# Main.net
KiCad netlist of a schematic drawn in Altium Designer
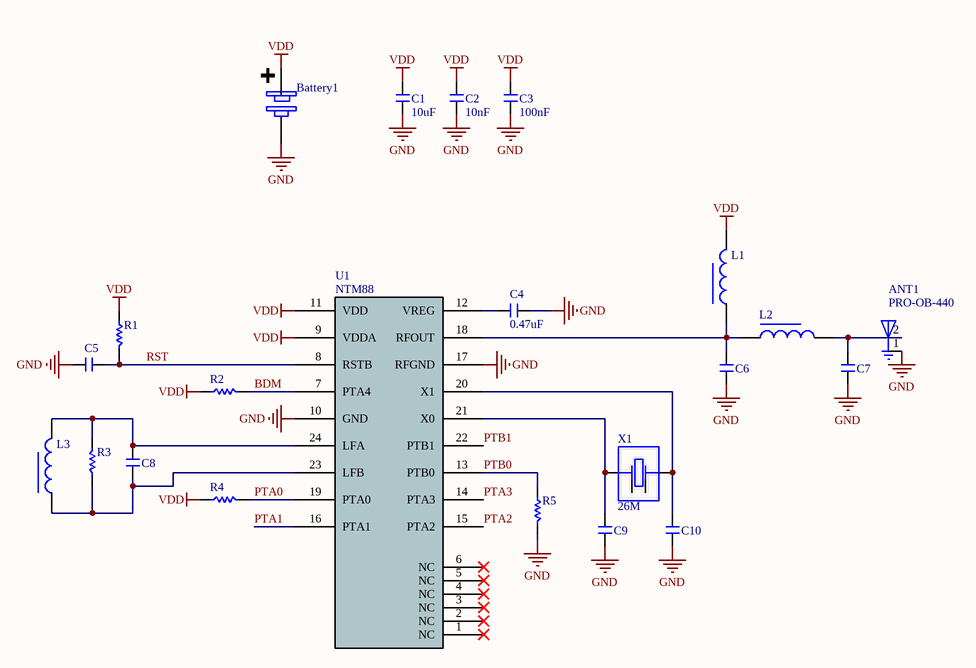
[diagram p0: Main.SchDoc]

(export (version "E")
  (design (tool "Eeschema 10.0.6"))
  (components
    (comp (ref "ANT1")
      (value "PRO-OB-440")
      (footprint "PRO-OB-440")
      (libsource (lib "Antenna") (part "PRO-OB-440"))
    )
    (comp (ref "Battery1")
      (value "Battery Button Cell")
      (footprint "CR1220_B")
      (description "Mini Battery")
      (libsource (lib "Battery Holder") (part "Battery Button Cell"))
    )
    (comp (ref "C1")
      (value "10uF")
      (footprint "C 0603")
      (description "Non-polar patch capacitor")
      (fields (field (name "版权归属") "源创客"))
      (libsource (lib "Passive (Resistor-Capacitor-Inductor-Veristor-Ferrite)") (part "C"))
    )
    (comp (ref "C2")
      (value "10nF")
      (footprint "C 0603")
      (description "Non-polar patch capacitor")
      (fields (field (name "版权归属") "源创客"))
      (libsource (lib "Passive (Resistor-Capacitor-Inductor-Veristor-Ferrite)") (part "C"))
    )
    (comp (ref "C3")
      (value "100nF")
      (footprint "C 0603")
      (description "Non-polar patch capacitor")
      (fields (field (name "版权归属") "源创客"))
      (libsource (lib "Passive (Resistor-Capacitor-Inductor-Veristor-Ferrite)") (part "C"))
    )
    (comp (ref "C4")
      (value "0.47uF")
      (footprint "C 0603")
      (description "Non-polar patch capacitor")
      (fields (field (name "版权归属") "源创客"))
      (libsource (lib "Passive (Resistor-Capacitor-Inductor-Veristor-Ferrite)") (part "C"))
    )
    (comp (ref "C5")
      (value "?")
      (footprint "C 0603")
      (description "Non-polar patch capacitor")
      (fields (field (name "版权归属") "源创客"))
      (libsource (lib "Passive (Resistor-Capacitor-Inductor-Veristor-Ferrite)") (part "C"))
    )
    (comp (ref "C6")
      (value "?")
      (footprint "C 0603")
      (description "Non-polar patch capacitor")
      (fields (field (name "版权归属") "源创客"))
      (libsource (lib "Passive (Resistor-Capacitor-Inductor-Veristor-Ferrite)") (part "C"))
    )
    (comp (ref "C7")
      (value "?")
      (footprint "C 0603")
      (description "Non-polar patch capacitor")
      (fields (field (name "版权归属") "源创客"))
      (libsource (lib "Passive (Resistor-Capacitor-Inductor-Veristor-Ferrite)") (part "C"))
    )
    (comp (ref "C8")
      (value "?")
      (footprint "C 0603")
      (description "Non-polar patch capacitor")
      (fields (field (name "版权归属") "源创客"))
      (libsource (lib "Passive (Resistor-Capacitor-Inductor-Veristor-Ferrite)") (part "C"))
    )
    (comp (ref "C9")
      (value "CRYSTAL REC")
      (footprint "C 0603")
      (description "Non-polar patch capacitor")
      (fields (field (name "版权归属") "源创客"))
      (libsource (lib "Passive (Resistor-Capacitor-Inductor-Veristor-Ferrite)") (part "C"))
    )
    (comp (ref "C10")
      (value "CRYSTAL REC")
      (footprint "C 0603")
      (description "Non-polar patch capacitor")
      (fields (field (name "版权归属") "源创客"))
      (libsource (lib "Passive (Resistor-Capacitor-Inductor-Veristor-Ferrite)") (part "C"))
    )
    (comp (ref "L1")
      (value "?uH")
      (footprint "L 0603")
      (description "Low power chip inductor")
      (fields (field (name "版权归属") "源创客"))
      (libsource (lib "Passive (Resistor-Capacitor-Inductor-Veristor-Ferrite)") (part "L"))
    )
    (comp (ref "L2")
      (value "?uH")
      (footprint "L 0603")
      (description "Low power chip inductor")
      (fields (field (name "版权归属") "源创客"))
      (libsource (lib "Passive (Resistor-Capacitor-Inductor-Veristor-Ferrite)") (part "L"))
    )
    (comp (ref "L3")
      (value "?uH")
      (footprint "L 0603")
      (description "Low power chip inductor")
      (fields (field (name "版权归属") "源创客"))
      (libsource (lib "Passive (Resistor-Capacitor-Inductor-Veristor-Ferrite)") (part "L"))
    )
    (comp (ref "R1")
      (value "?")
      (footprint "R 0603")
      (description "Chip resistor")
      (fields (field (name "版权归属") "源创客"))
      (libsource (lib "Passive (Resistor-Capacitor-Inductor-Veristor-Ferrite)") (part "R"))
    )
    (comp (ref "R2")
      (value "?")
      (footprint "R 0603")
      (description "Chip resistor")
      (fields (field (name "版权归属") "源创客"))
      (libsource (lib "Passive (Resistor-Capacitor-Inductor-Veristor-Ferrite)") (part "R"))
    )
    (comp (ref "R3")
      (value "?")
      (footprint "R 0603")
      (description "Chip resistor")
      (fields (field (name "版权归属") "源创客"))
      (libsource (lib "Passive (Resistor-Capacitor-Inductor-Veristor-Ferrite)") (part "R"))
    )
    (comp (ref "R4")
      (value "?")
      (footprint "R 0603")
      (description "Chip resistor")
      (fields (field (name "版权归属") "源创客"))
      (libsource (lib "Passive (Resistor-Capacitor-Inductor-Veristor-Ferrite)") (part "R"))
    )
    (comp (ref "R5")
      (value "1K")
      (footprint "R 0603")
      (description "Chip resistor")
      (fields (field (name "版权归属") "源创客"))
      (libsource (lib "Passive (Resistor-Capacitor-Inductor-Veristor-Ferrite)") (part "R"))
    )
    (comp (ref "U1")
      (value "NTM88")
      (footprint "QFN24")
      (description "TPMS Sensor")
      (libsource (lib "Integrated Circuit") (part "NTM88"))
    )
    (comp (ref "X1")
      (value "26M")
      (footprint "XTAL-2520-4")
      (description "4-Pin crystal")
      (fields (field (name "版权归属") "源创客"))
      (libsource (lib "Crystal Oscillator") (part "XTAL-4"))
    )
  )
  (nets
    (net (code "1") (name "/BDM") (class "Default")
      (node (ref "R2") (pin "2") (pinfunction "2_2") (pintype "passive"))
      (node (ref "U1") (pin "7") (pinfunction "PTA4_7") (pintype "passive"))
    )
    (net (code "2") (name "/PTA0") (class "Default")
      (node (ref "R4") (pin "2") (pinfunction "2_2") (pintype "passive"))
      (node (ref "U1") (pin "19") (pinfunction "PTA0_19") (pintype "passive"))
    )
    (net (code "3") (name "/PTA1") (class "Default")
      (node (ref "U1") (pin "16") (pinfunction "PTA1_16") (pintype "passive"))
    )
    (net (code "4") (name "/PTA2") (class "Default")
      (node (ref "U1") (pin "15") (pinfunction "PTA2_15") (pintype "passive"))
    )
    (net (code "5") (name "/PTA3") (class "Default")
      (node (ref "U1") (pin "14") (pinfunction "PTA3_14") (pintype "passive"))
    )
    (net (code "6") (name "/PTB0") (class "Default")
      (node (ref "R5") (pin "1") (pinfunction "1_1") (pintype "passive"))
      (node (ref "U1") (pin "13") (pinfunction "PTB0_13") (pintype "passive"))
    )
    (net (code "7") (name "/PTB1") (class "Default")
      (node (ref "U1") (pin "22") (pinfunction "PTB1_22") (pintype "passive"))
    )
    (net (code "8") (name "/RST") (class "Default")
      (node (ref "C5") (pin "2") (pinfunction "2_2") (pintype "passive"))
      (node (ref "R1") (pin "2") (pinfunction "2_2") (pintype "passive"))
      (node (ref "U1") (pin "8") (pinfunction "RSTB_8") (pintype "passive"))
    )
    (net (code "9") (name "GND") (class "Default")
      (node (ref "ANT1") (pin "1") (pinfunction "GND_1") (pintype "power_in"))
      (node (ref "Battery1") (pin "2") (pinfunction "-_2") (pintype "passive"))
      (node (ref "C1") (pin "1") (pinfunction "1_1") (pintype "passive"))
      (node (ref "C10") (pin "1") (pinfunction "1_1") (pintype "passive"))
      (node (ref "C2") (pin "1") (pinfunction "1_1") (pintype "passive"))
      (node (ref "C3") (pin "1") (pinfunction "1_1") (pintype "passive"))
      (node (ref "C4") (pin "1") (pinfunction "1_1") (pintype "passive"))
      (node (ref "C5") (pin "1") (pinfunction "1_1") (pintype "passive"))
      (node (ref "C6") (pin "1") (pinfunction "1_1") (pintype "passive"))
      (node (ref "C7") (pin "1") (pinfunction "1_1") (pintype "passive"))
      (node (ref "C9") (pin "1") (pinfunction "1_1") (pintype "passive"))
      (node (ref "R5") (pin "2") (pinfunction "2_2") (pintype "passive"))
      (node (ref "U1") (pin "10") (pinfunction "GND_10") (pintype "passive"))
      (node (ref "U1") (pin "17") (pinfunction "RFGND_17") (pintype "passive"))
    )
    (net (code "10") (name "Net-(ANT1-FEED)") (class "Default")
      (node (ref "ANT1") (pin "2") (pinfunction "FEED_2") (pintype "passive"))
      (node (ref "C7") (pin "2") (pinfunction "2_2") (pintype "passive"))
      (node (ref "L2") (pin "2") (pinfunction "2_2") (pintype "passive"))
    )
    (net (code "11") (name "Net-(U1-LFA)") (class "Default")
      (node (ref "C8") (pin "2") (pinfunction "2_2") (pintype "passive"))
      (node (ref "L3") (pin "2") (pinfunction "2_2") (pintype "passive"))
      (node (ref "R3") (pin "2") (pinfunction "2_2") (pintype "passive"))
      (node (ref "U1") (pin "24") (pinfunction "LFA_24") (pintype "passive"))
    )
    (net (code "12") (name "Net-(U1-LFB)") (class "Default")
      (node (ref "C8") (pin "1") (pinfunction "1_1") (pintype "passive"))
      (node (ref "L3") (pin "1") (pinfunction "1_1") (pintype "passive"))
      (node (ref "R3") (pin "1") (pinfunction "1_1") (pintype "passive"))
      (node (ref "U1") (pin "23") (pinfunction "LFB_23") (pintype "passive"))
    )
    (net (code "13") (name "Net-(U1-RFOUT)") (class "Default")
      (node (ref "C6") (pin "2") (pinfunction "2_2") (pintype "passive"))
      (node (ref "L1") (pin "1") (pinfunction "1_1") (pintype "passive"))
      (node (ref "L2") (pin "1") (pinfunction "1_1") (pintype "passive"))
      (node (ref "U1") (pin "18") (pinfunction "RFOUT_18") (pintype "passive"))
    )
    (net (code "14") (name "Net-(U1-VREG)") (class "Default")
      (node (ref "C4") (pin "2") (pinfunction "2_2") (pintype "passive"))
      (node (ref "U1") (pin "12") (pinfunction "VREG_12") (pintype "passive"))
    )
    (net (code "15") (name "Net-(U1-X0)") (class "Default")
      (node (ref "C9") (pin "2") (pinfunction "2_2") (pintype "passive"))
      (node (ref "U1") (pin "21") (pinfunction "X0_21") (pintype "passive"))
      (node (ref "X1") (pin "1") (pinfunction "1_1") (pintype "passive"))
    )
    (net (code "16") (name "Net-(U1-X1)") (class "Default")
      (node (ref "C10") (pin "2") (pinfunction "2_2") (pintype "passive"))
      (node (ref "U1") (pin "20") (pinfunction "X1_20") (pintype "passive"))
      (node (ref "X1") (pin "3") (pinfunction "3_3") (pintype "passive"))
    )
    (net (code "17") (name "VDD") (class "Default")
      (node (ref "Battery1") (pin "1") (pinfunction "+_1") (pintype "passive"))
      (node (ref "C1") (pin "2") (pinfunction "2_2") (pintype "passive"))
      (node (ref "C2") (pin "2") (pinfunction "2_2") (pintype "passive"))
      (node (ref "C3") (pin "2") (pinfunction "2_2") (pintype "passive"))
      (node (ref "L1") (pin "2") (pinfunction "2_2") (pintype "passive"))
      (node (ref "R1") (pin "1") (pinfunction "1_1") (pintype "passive"))
      (node (ref "R2") (pin "1") (pinfunction "1_1") (pintype "passive"))
      (node (ref "R4") (pin "1") (pinfunction "1_1") (pintype "passive"))
      (node (ref "U1") (pin "11") (pinfunction "VDD_11") (pintype "passive"))
      (node (ref "U1") (pin "9") (pinfunction "VDDA_9") (pintype "passive"))
    )
    (net (code "18") (name "unconnected-(U1-NC-Pad1)") (class "Default")
      (node (ref "U1") (pin "1") (pinfunction "NC_1") (pintype "passive+no_connect"))
    )
    (net (code "19") (name "unconnected-(U1-NC-Pad2)") (class "Default")
      (node (ref "U1") (pin "2") (pinfunction "NC_2") (pintype "passive+no_connect"))
    )
    (net (code "20") (name "unconnected-(U1-NC-Pad3)") (class "Default")
      (node (ref "U1") (pin "3") (pinfunction "NC_3") (pintype "passive+no_connect"))
    )
    (net (code "21") (name "unconnected-(U1-NC-Pad4)") (class "Default")
      (node (ref "U1") (pin "4") (pinfunction "NC_4") (pintype "passive+no_connect"))
    )
    (net (code "22") (name "unconnected-(U1-NC-Pad5)") (class "Default")
      (node (ref "U1") (pin "5") (pinfunction "NC_5") (pintype "passive+no_connect"))
    )
    (net (code "23") (name "unconnected-(U1-NC-Pad6)") (class "Default")
      (node (ref "U1") (pin "6") (pinfunction "NC_6") (pintype "passive+no_connect"))
    )
    (net (code "24") (name "unconnected-(X1-Pad2)") (class "Default")
      (node (ref "X1") (pin "2") (pinfunction "2_2") (pintype "passive"))
    )
    (net (code "25") (name "unconnected-(X1-Pad4)") (class "Default")
      (node (ref "X1") (pin "4") (pinfunction "4_4") (pintype "passive"))
    )
  )
)
